# cnc_shield_v2.net
KiCad netlist of a schematic drawn in EAGLE
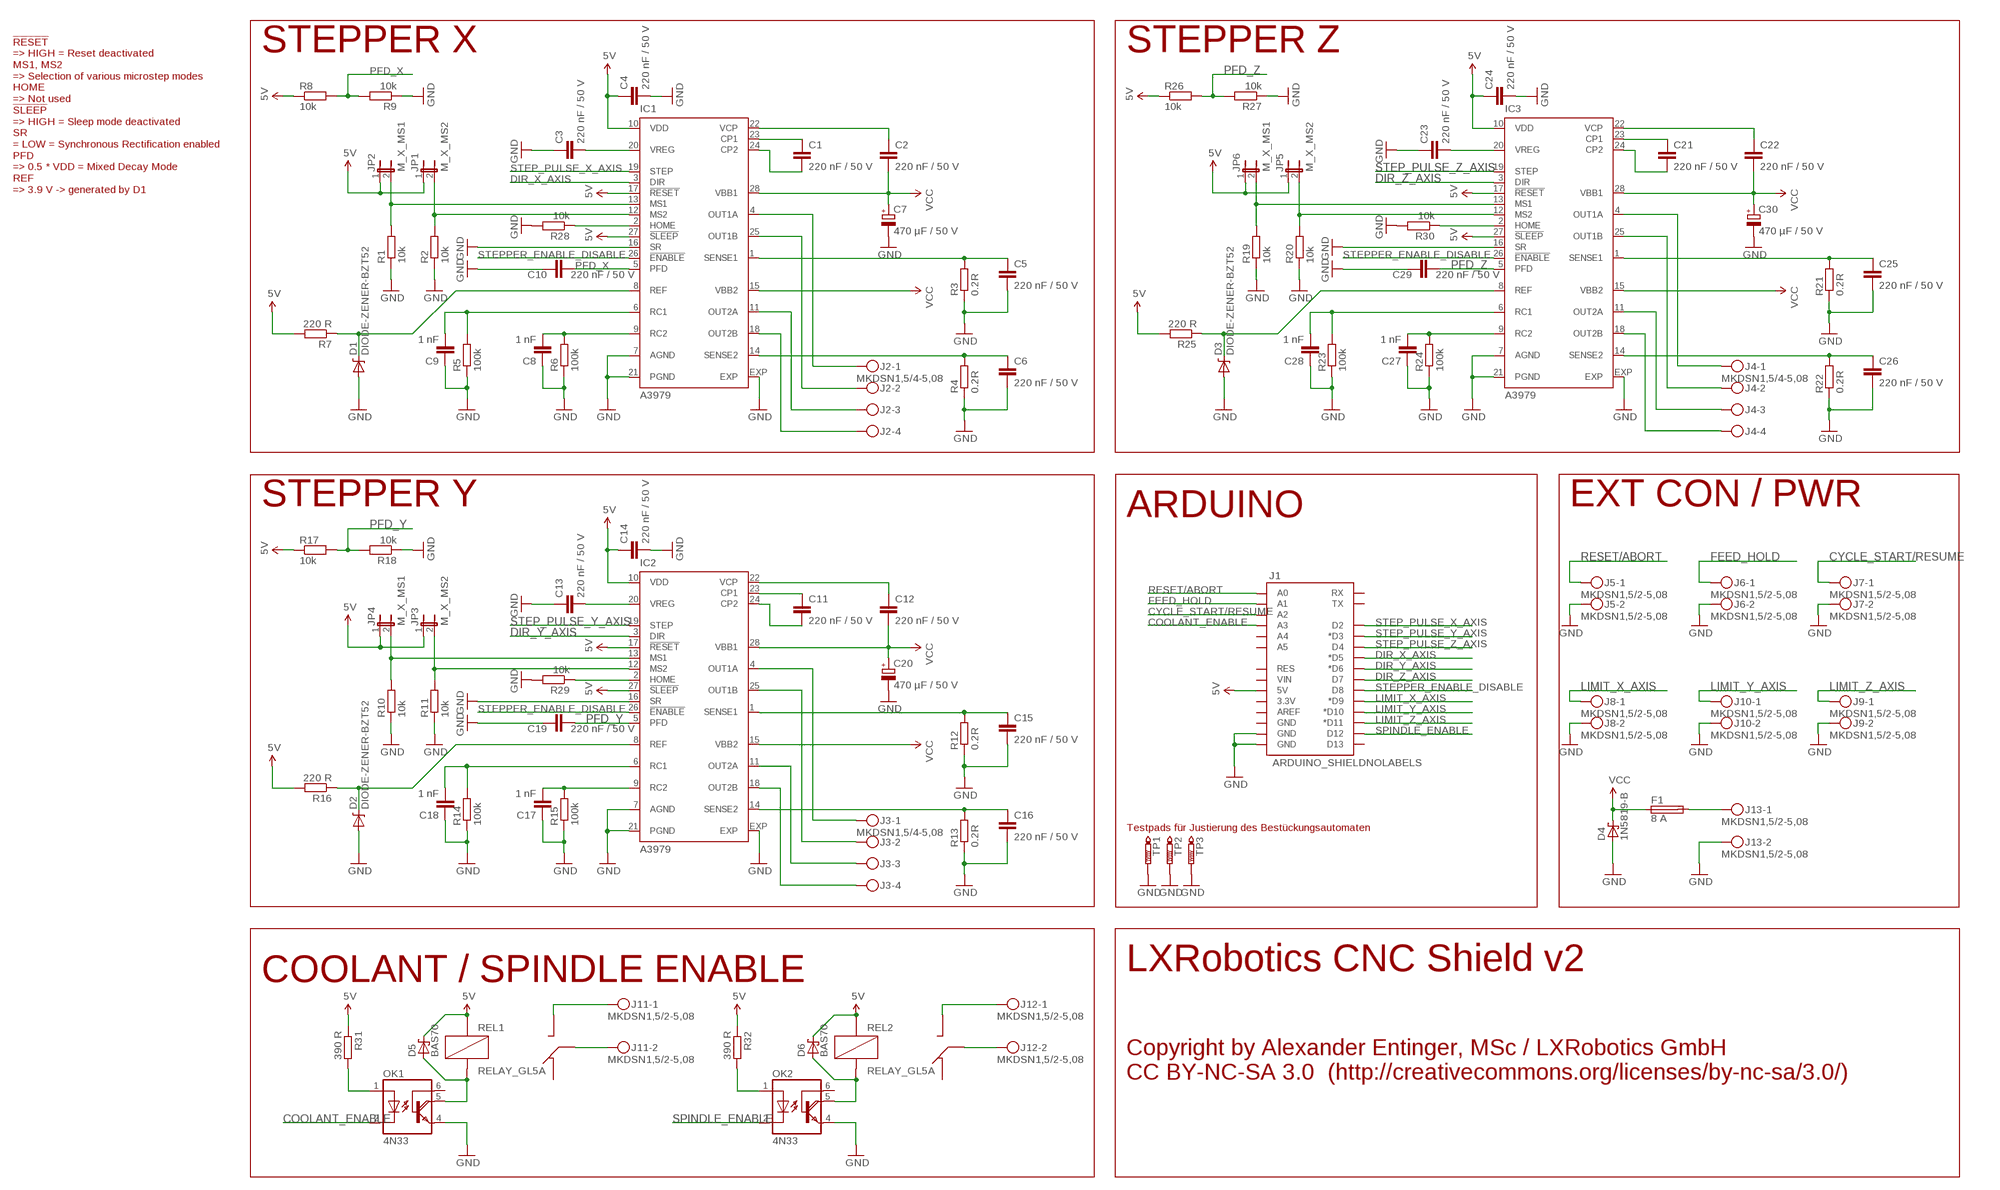
[diagram p0: schematic, sheet 1]

(export (version "E")
  (design (tool "Eeschema 10.0.6"))
  (components
    (comp (ref "C1")
      (value "220 nF / 50 V")
      (footprint "eagle-import:C0805K")
      (libsource (lib "eagle-import") (part "C-EUC0805K"))
    )
    (comp (ref "C2")
      (value "220 nF / 50 V")
      (footprint "eagle-import:C0805K")
      (libsource (lib "eagle-import") (part "C-EUC0805K"))
    )
    (comp (ref "C3")
      (value "220 nF / 50 V")
      (footprint "eagle-import:C0805K")
      (libsource (lib "eagle-import") (part "C-EUC0805K"))
    )
    (comp (ref "C4")
      (value "220 nF / 50 V")
      (footprint "eagle-import:C0805K")
      (libsource (lib "eagle-import") (part "C-EUC0805K"))
    )
    (comp (ref "C5")
      (value "220 nF / 50 V")
      (footprint "eagle-import:C0805K")
      (libsource (lib "eagle-import") (part "C-EUC0805K"))
    )
    (comp (ref "C6")
      (value "220 nF / 50 V")
      (footprint "eagle-import:C0805K")
      (libsource (lib "eagle-import") (part "C-EUC0805K"))
    )
    (comp (ref "C7")
      (value "470 µF / 50 V")
      (footprint "eagle-import:E5-13")
      (libsource (lib "eagle-import") (part "CPOL-EUE5-13"))
    )
    (comp (ref "C8")
      (value "1 nF")
      (footprint "eagle-import:C0805K")
      (libsource (lib "eagle-import") (part "C-EUC0805K"))
    )
    (comp (ref "C9")
      (value "1 nF")
      (footprint "eagle-import:C0805K")
      (libsource (lib "eagle-import") (part "C-EUC0805K"))
    )
    (comp (ref "C10")
      (value "220 nF / 50 V")
      (footprint "eagle-import:C0805K")
      (libsource (lib "eagle-import") (part "C-EUC0805K"))
    )
    (comp (ref "C11")
      (value "220 nF / 50 V")
      (footprint "eagle-import:C0805K")
      (libsource (lib "eagle-import") (part "C-EUC0805K"))
    )
    (comp (ref "C12")
      (value "220 nF / 50 V")
      (footprint "eagle-import:C0805K")
      (libsource (lib "eagle-import") (part "C-EUC0805K"))
    )
    (comp (ref "C13")
      (value "220 nF / 50 V")
      (footprint "eagle-import:C0805K")
      (libsource (lib "eagle-import") (part "C-EUC0805K"))
    )
    (comp (ref "C14")
      (value "220 nF / 50 V")
      (footprint "eagle-import:C0805K")
      (libsource (lib "eagle-import") (part "C-EUC0805K"))
    )
    (comp (ref "C15")
      (value "220 nF / 50 V")
      (footprint "eagle-import:C0805K")
      (libsource (lib "eagle-import") (part "C-EUC0805K"))
    )
    (comp (ref "C16")
      (value "220 nF / 50 V")
      (footprint "eagle-import:C0805K")
      (libsource (lib "eagle-import") (part "C-EUC0805K"))
    )
    (comp (ref "C17")
      (value "1 nF")
      (footprint "eagle-import:C0805K")
      (libsource (lib "eagle-import") (part "C-EUC0805K"))
    )
    (comp (ref "C18")
      (value "1 nF")
      (footprint "eagle-import:C0805K")
      (libsource (lib "eagle-import") (part "C-EUC0805K"))
    )
    (comp (ref "C19")
      (value "220 nF / 50 V")
      (footprint "eagle-import:C0805K")
      (libsource (lib "eagle-import") (part "C-EUC0805K"))
    )
    (comp (ref "C20")
      (value "470 µF / 50 V")
      (footprint "eagle-import:E5-13")
      (libsource (lib "eagle-import") (part "CPOL-EUE5-13"))
    )
    (comp (ref "C21")
      (value "220 nF / 50 V")
      (footprint "eagle-import:C0805K")
      (libsource (lib "eagle-import") (part "C-EUC0805K"))
    )
    (comp (ref "C22")
      (value "220 nF / 50 V")
      (footprint "eagle-import:C0805K")
      (libsource (lib "eagle-import") (part "C-EUC0805K"))
    )
    (comp (ref "C23")
      (value "220 nF / 50 V")
      (footprint "eagle-import:C0805K")
      (libsource (lib "eagle-import") (part "C-EUC0805K"))
    )
    (comp (ref "C24")
      (value "220 nF / 50 V")
      (footprint "eagle-import:C0805K")
      (libsource (lib "eagle-import") (part "C-EUC0805K"))
    )
    (comp (ref "C25")
      (value "220 nF / 50 V")
      (footprint "eagle-import:C0805K")
      (libsource (lib "eagle-import") (part "C-EUC0805K"))
    )
    (comp (ref "C26")
      (value "220 nF / 50 V")
      (footprint "eagle-import:C0805K")
      (libsource (lib "eagle-import") (part "C-EUC0805K"))
    )
    (comp (ref "C27")
      (value "1 nF")
      (footprint "eagle-import:C0805K")
      (libsource (lib "eagle-import") (part "C-EUC0805K"))
    )
    (comp (ref "C28")
      (value "1 nF")
      (footprint "eagle-import:C0805K")
      (libsource (lib "eagle-import") (part "C-EUC0805K"))
    )
    (comp (ref "C29")
      (value "220 nF / 50 V")
      (footprint "eagle-import:C0805K")
      (libsource (lib "eagle-import") (part "C-EUC0805K"))
    )
    (comp (ref "C30")
      (value "470 µF / 50 V")
      (footprint "eagle-import:E5-13")
      (libsource (lib "eagle-import") (part "CPOL-EUE5-13"))
    )
    (comp (ref "D1")
      (value "DIODE-ZENER-BZT52")
      (footprint "eagle-import:SOD-323")
      (libsource (lib "eagle-import") (part "DIODE-ZENER-BZT52"))
    )
    (comp (ref "D2")
      (value "DIODE-ZENER-BZT52")
      (footprint "eagle-import:SOD-323")
      (libsource (lib "eagle-import") (part "DIODE-ZENER-BZT52"))
    )
    (comp (ref "D3")
      (value "DIODE-ZENER-BZT52")
      (footprint "eagle-import:SOD-323")
      (libsource (lib "eagle-import") (part "DIODE-ZENER-BZT52"))
    )
    (comp (ref "D4")
      (value "1N5819-B")
      (footprint "eagle-import:DO41-7.6")
      (libsource (lib "eagle-import") (part "1N5819-B"))
    )
    (comp (ref "D5")
      (value "BAS70")
      (footprint "eagle-import:SOT23")
      (libsource (lib "eagle-import") (part "BAS70"))
    )
    (comp (ref "D6")
      (value "BAS70")
      (footprint "eagle-import:SOT23")
      (libsource (lib "eagle-import") (part "BAS70"))
    )
    (comp (ref "F1")
      (value "8 A")
      (footprint "eagle-import:SH22,5")
      (fields (field (name "MF") "SCHURTER") (field (name "MPN") "0031.8201"))
      (libsource (lib "eagle-import") (part "SH22,5"))
    )
    (comp (ref "IC1")
      (value "A3979")
      (footprint "eagle-import:TSSOP28")
      (libsource (lib "eagle-import") (part "A3979"))
    )
    (comp (ref "IC2")
      (value "A3979")
      (footprint "eagle-import:TSSOP28")
      (libsource (lib "eagle-import") (part "A3979"))
    )
    (comp (ref "IC3")
      (value "A3979")
      (footprint "eagle-import:TSSOP28")
      (libsource (lib "eagle-import") (part "A3979"))
    )
    (comp (ref "J1")
      (value "ARDUINO_SHIELDNOLABELS")
      (footprint "eagle-import:DUEMILANOVE_SHIELD_NOLABELS")
      (libsource (lib "eagle-import") (part "ARDUINO_SHIELDNOLABELS"))
    )
    (comp (ref "J2")
      (value "MKDSN1,5/4-5,08")
      (footprint "eagle-import:MKDSN1,5_4-5,08")
      (fields (field (name "MPN") "SMKDSN1,5/4-5,08"))
      (libsource (lib "eagle-import") (part "MKDSN1,5/4-5,08"))
    )
    (comp (ref "J3")
      (value "MKDSN1,5/4-5,08")
      (footprint "eagle-import:MKDSN1,5_4-5,08")
      (fields (field (name "MPN") "SMKDSN1,5/4-5,08"))
      (libsource (lib "eagle-import") (part "MKDSN1,5/4-5,08"))
    )
    (comp (ref "J4")
      (value "MKDSN1,5/4-5,08")
      (footprint "eagle-import:MKDSN1,5_4-5,08")
      (fields (field (name "MPN") "SMKDSN1,5/4-5,08"))
      (libsource (lib "eagle-import") (part "MKDSN1,5/4-5,08"))
    )
    (comp (ref "J5")
      (value "MKDSN1,5/2-5,08")
      (footprint "eagle-import:MKDSN1,5_2-5,08")
      (fields (field (name "MPN") "MKDSN 1,5/2-5.08"))
      (libsource (lib "eagle-import") (part "MKDSN1,5/2-5,08"))
    )
    (comp (ref "J6")
      (value "MKDSN1,5/2-5,08")
      (footprint "eagle-import:MKDSN1,5_2-5,08")
      (fields (field (name "MPN") "MKDSN 1,5/2-5.08"))
      (libsource (lib "eagle-import") (part "MKDSN1,5/2-5,08"))
    )
    (comp (ref "J7")
      (value "MKDSN1,5/2-5,08")
      (footprint "eagle-import:MKDSN1,5_2-5,08")
      (fields (field (name "MPN") "MKDSN 1,5/2-5.08"))
      (libsource (lib "eagle-import") (part "MKDSN1,5/2-5,08"))
    )
    (comp (ref "J8")
      (value "MKDSN1,5/2-5,08")
      (footprint "eagle-import:MKDSN1,5_2-5,08")
      (fields (field (name "MPN") "MKDSN 1,5/2-5.08"))
      (libsource (lib "eagle-import") (part "MKDSN1,5/2-5,08"))
    )
    (comp (ref "J9")
      (value "MKDSN1,5/2-5,08")
      (footprint "eagle-import:MKDSN1,5_2-5,08")
      (fields (field (name "MPN") "MKDSN 1,5/2-5.08"))
      (libsource (lib "eagle-import") (part "MKDSN1,5/2-5,08"))
    )
    (comp (ref "J10")
      (value "MKDSN1,5/2-5,08")
      (footprint "eagle-import:MKDSN1,5_2-5,08")
      (fields (field (name "MPN") "MKDSN 1,5/2-5.08"))
      (libsource (lib "eagle-import") (part "MKDSN1,5/2-5,08"))
    )
    (comp (ref "J11")
      (value "MKDSN1,5/2-5,08")
      (footprint "eagle-import:MKDSN1,5_2-5,08")
      (fields (field (name "MPN") "MKDSN 1,5/2-5.08"))
      (libsource (lib "eagle-import") (part "MKDSN1,5/2-5,08"))
    )
    (comp (ref "J12")
      (value "MKDSN1,5/2-5,08")
      (footprint "eagle-import:MKDSN1,5_2-5,08")
      (fields (field (name "MPN") "MKDSN 1,5/2-5.08"))
      (libsource (lib "eagle-import") (part "MKDSN1,5/2-5,08"))
    )
    (comp (ref "J13")
      (value "MKDSN1,5/2-5,08")
      (footprint "eagle-import:MKDSN1,5_2-5,08")
      (fields (field (name "MPN") "MKDSN 1,5/2-5.08"))
      (libsource (lib "eagle-import") (part "MKDSN1,5/2-5,08"))
    )
    (comp (ref "JP1")
      (value "M_X_MS2")
      (footprint "eagle-import:JP1")
      (libsource (lib "eagle-import") (part "JP1E"))
    )
    (comp (ref "JP2")
      (value "M_X_MS1")
      (footprint "eagle-import:JP1")
      (libsource (lib "eagle-import") (part "JP1E"))
    )
    (comp (ref "JP3")
      (value "M_X_MS2")
      (footprint "eagle-import:JP1")
      (libsource (lib "eagle-import") (part "JP1E"))
    )
    (comp (ref "JP4")
      (value "M_X_MS1")
      (footprint "eagle-import:JP1")
      (libsource (lib "eagle-import") (part "JP1E"))
    )
    (comp (ref "JP5")
      (value "M_X_MS2")
      (footprint "eagle-import:JP1")
      (libsource (lib "eagle-import") (part "JP1E"))
    )
    (comp (ref "JP6")
      (value "M_X_MS1")
      (footprint "eagle-import:JP1")
      (libsource (lib "eagle-import") (part "JP1E"))
    )
    (comp (ref "OK1")
      (value "4N33")
      (footprint "eagle-import:DIL06")
      (fields (field (name "MF") "VISHAY/TELEFUNKEN"))
      (libsource (lib "eagle-import") (part "4N33"))
    )
    (comp (ref "OK2")
      (value "4N33")
      (footprint "eagle-import:DIL06")
      (fields (field (name "MF") "VISHAY/TELEFUNKEN"))
      (libsource (lib "eagle-import") (part "4N33"))
    )
    (comp (ref "R1")
      (value "10k")
      (footprint "eagle-import:R0805")
      (libsource (lib "eagle-import") (part "R-EU_R0805"))
    )
    (comp (ref "R2")
      (value "10k")
      (footprint "eagle-import:R0805")
      (libsource (lib "eagle-import") (part "R-EU_R0805"))
    )
    (comp (ref "R3")
      (value "0.2R")
      (footprint "eagle-import:R2512")
      (libsource (lib "eagle-import") (part "R-EU_R2512"))
    )
    (comp (ref "R4")
      (value "0.2R")
      (footprint "eagle-import:R2512")
      (libsource (lib "eagle-import") (part "R-EU_R2512"))
    )
    (comp (ref "R5")
      (value "100k")
      (footprint "eagle-import:R0805")
      (libsource (lib "eagle-import") (part "R-EU_R0805"))
    )
    (comp (ref "R6")
      (value "100k")
      (footprint "eagle-import:R0805")
      (libsource (lib "eagle-import") (part "R-EU_R0805"))
    )
    (comp (ref "R7")
      (value "220 R")
      (footprint "eagle-import:R0805")
      (libsource (lib "eagle-import") (part "R-EU_R0805"))
    )
    (comp (ref "R8")
      (value "10k")
      (footprint "eagle-import:R0805")
      (libsource (lib "eagle-import") (part "R-EU_R0805"))
    )
    (comp (ref "R9")
      (value "10k")
      (footprint "eagle-import:R0805")
      (libsource (lib "eagle-import") (part "R-EU_R0805"))
    )
    (comp (ref "R10")
      (value "10k")
      (footprint "eagle-import:R0805")
      (libsource (lib "eagle-import") (part "R-EU_R0805"))
    )
    (comp (ref "R11")
      (value "10k")
      (footprint "eagle-import:R0805")
      (libsource (lib "eagle-import") (part "R-EU_R0805"))
    )
    (comp (ref "R12")
      (value "0.2R")
      (footprint "eagle-import:R2512")
      (libsource (lib "eagle-import") (part "R-EU_R2512"))
    )
    (comp (ref "R13")
      (value "0.2R")
      (footprint "eagle-import:R2512")
      (libsource (lib "eagle-import") (part "R-EU_R2512"))
    )
    (comp (ref "R14")
      (value "100k")
      (footprint "eagle-import:R0805")
      (libsource (lib "eagle-import") (part "R-EU_R0805"))
    )
    (comp (ref "R15")
      (value "100k")
      (footprint "eagle-import:R0805")
      (libsource (lib "eagle-import") (part "R-EU_R0805"))
    )
    (comp (ref "R16")
      (value "220 R")
      (footprint "eagle-import:R0805")
      (libsource (lib "eagle-import") (part "R-EU_R0805"))
    )
    (comp (ref "R17")
      (value "10k")
      (footprint "eagle-import:R0805")
      (libsource (lib "eagle-import") (part "R-EU_R0805"))
    )
    (comp (ref "R18")
      (value "10k")
      (footprint "eagle-import:R0805")
      (libsource (lib "eagle-import") (part "R-EU_R0805"))
    )
    (comp (ref "R19")
      (value "10k")
      (footprint "eagle-import:R0805")
      (libsource (lib "eagle-import") (part "R-EU_R0805"))
    )
    (comp (ref "R20")
      (value "10k")
      (footprint "eagle-import:R0805")
      (libsource (lib "eagle-import") (part "R-EU_R0805"))
    )
    (comp (ref "R21")
      (value "0.2R")
      (footprint "eagle-import:R2512")
      (libsource (lib "eagle-import") (part "R-EU_R2512"))
    )
    (comp (ref "R22")
      (value "0.2R")
      (footprint "eagle-import:R2512")
      (libsource (lib "eagle-import") (part "R-EU_R2512"))
    )
    (comp (ref "R23")
      (value "100k")
      (footprint "eagle-import:R0805")
      (libsource (lib "eagle-import") (part "R-EU_R0805"))
    )
    (comp (ref "R24")
      (value "100k")
      (footprint "eagle-import:R0805")
      (libsource (lib "eagle-import") (part "R-EU_R0805"))
    )
    (comp (ref "R25")
      (value "220 R")
      (footprint "eagle-import:R0805")
      (libsource (lib "eagle-import") (part "R-EU_R0805"))
    )
    (comp (ref "R26")
      (value "10k")
      (footprint "eagle-import:R0805")
      (libsource (lib "eagle-import") (part "R-EU_R0805"))
    )
    (comp (ref "R27")
      (value "10k")
      (footprint "eagle-import:R0805")
      (libsource (lib "eagle-import") (part "R-EU_R0805"))
    )
    (comp (ref "R28")
      (value "10k")
      (footprint "eagle-import:R0805")
      (libsource (lib "eagle-import") (part "R-EU_R0805"))
    )
    (comp (ref "R29")
      (value "10k")
      (footprint "eagle-import:R0805")
      (libsource (lib "eagle-import") (part "R-EU_R0805"))
    )
    (comp (ref "R30")
      (value "10k")
      (footprint "eagle-import:R0805")
      (libsource (lib "eagle-import") (part "R-EU_R0805"))
    )
    (comp (ref "R31")
      (value "390 R")
      (footprint "eagle-import:R0805")
      (libsource (lib "eagle-import") (part "R-EU_R0805"))
    )
    (comp (ref "R32")
      (value "390 R")
      (footprint "eagle-import:R0805")
      (libsource (lib "eagle-import") (part "R-EU_R0805"))
    )
    (comp (ref "REL1")
      (value "RELAY_GL5A")
      (footprint "eagle-import:RELAY_GL5A")
      (libsource (lib "eagle-import") (part "RELAY_GL5A"))
    )
    (comp (ref "REL2")
      (value "RELAY_GL5A")
      (footprint "eagle-import:RELAY_GL5A")
      (libsource (lib "eagle-import") (part "RELAY_GL5A"))
    )
    (comp (ref "TP1")
      (value "PTR1B1,27")
      (footprint "eagle-import:B1,27")
      (libsource (lib "eagle-import") (part "PTR1B1,27"))
    )
    (comp (ref "TP2")
      (value "PTR1B1,27")
      (footprint "eagle-import:B1,27")
      (libsource (lib "eagle-import") (part "PTR1B1,27"))
    )
    (comp (ref "TP3")
      (value "PTR1B1,27")
      (footprint "eagle-import:B1,27")
      (libsource (lib "eagle-import") (part "PTR1B1,27"))
    )
  )
  (nets
    (net (code "1") (name "/COOLANT_ENABLE") (class "Default")
      (node (ref "J1") (pin "A3") (pinfunction "A3_A3") (pintype "bidirectional"))
      (node (ref "OK1") (pin "2") (pinfunction "C_2") (pintype "passive"))
    )
    (net (code "2") (name "/CYCLE_START{slash}RESUME") (class "Default")
      (node (ref "J1") (pin "A2") (pinfunction "A2_A2") (pintype "bidirectional"))
      (node (ref "J7") (pin "1") (pinfunction "KL_1") (pintype "passive"))
    )
    (net (code "3") (name "/DIR_X_AXIS") (class "Default")
      (node (ref "IC1") (pin "3") (pinfunction "DIR_3") (pintype "input"))
      (node (ref "J1") (pin "D5") (pinfunction "*D5_D5") (pintype "bidirectional"))
    )
    (net (code "4") (name "/DIR_Y_AXIS") (class "Default")
      (node (ref "IC2") (pin "3") (pinfunction "DIR_3") (pintype "input"))
      (node (ref "J1") (pin "D6") (pinfunction "*D6_D6") (pintype "bidirectional"))
    )
    (net (code "5") (name "/DIR_Z_AXIS") (class "Default")
      (node (ref "IC3") (pin "3") (pinfunction "DIR_3") (pintype "input"))
      (node (ref "J1") (pin "D7") (pinfunction "D7_D7") (pintype "bidirectional"))
    )
    (net (code "6") (name "/FEED_HOLD") (class "Default")
      (node (ref "J1") (pin "A1") (pinfunction "A1_A1") (pintype "bidirectional"))
      (node (ref "J6") (pin "1") (pinfunction "KL_1") (pintype "passive"))
    )
    (net (code "7") (name "/LIMIT_X_AXIS") (class "Default")
      (node (ref "J1") (pin "D9") (pinfunction "*D9_D9") (pintype "bidirectional"))
      (node (ref "J8") (pin "1") (pinfunction "KL_1") (pintype "passive"))
    )
    (net (code "8") (name "/LIMIT_Y_AXIS") (class "Default")
      (node (ref "J1") (pin "D10") (pinfunction "*D10_D10") (pintype "bidirectional"))
      (node (ref "J10") (pin "1") (pinfunction "KL_1") (pintype "passive"))
    )
    (net (code "9") (name "/LIMIT_Z_AXIS") (class "Default")
      (node (ref "J1") (pin "D11") (pinfunction "*D11_D11") (pintype "bidirectional"))
      (node (ref "J9") (pin "1") (pinfunction "KL_1") (pintype "passive"))
    )
    (net (code "10") (name "/PFD_X") (class "Default")
      (node (ref "C10") (pin "2") (pinfunction "2_2") (pintype "passive"))
      (node (ref "IC1") (pin "5") (pinfunction "PFD_5") (pintype "input"))
      (node (ref "R8") (pin "2") (pinfunction "2_2") (pintype "passive"))
      (node (ref "R9") (pin "2") (pinfunction "2_2") (pintype "passive"))
    )
    (net (code "11") (name "/PFD_Y") (class "Default")
      (node (ref "C19") (pin "2") (pinfunction "2_2") (pintype "passive"))
      (node (ref "IC2") (pin "5") (pinfunction "PFD_5") (pintype "input"))
      (node (ref "R17") (pin "2") (pinfunction "2_2") (pintype "passive"))
      (node (ref "R18") (pin "2") (pinfunction "2_2") (pintype "passive"))
    )
    (net (code "12") (name "/PFD_Z") (class "Default")
      (node (ref "C29") (pin "2") (pinfunction "2_2") (pintype "passive"))
      (node (ref "IC3") (pin "5") (pinfunction "PFD_5") (pintype "input"))
      (node (ref "R26") (pin "2") (pinfunction "2_2") (pintype "passive"))
      (node (ref "R27") (pin "2") (pinfunction "2_2") (pintype "passive"))
    )
    (net (code "13") (name "/RESET{slash}ABORT") (class "Default")
      (node (ref "J1") (pin "A0") (pinfunction "A0_A0") (pintype "bidirectional"))
      (node (ref "J5") (pin "1") (pinfunction "KL_1") (pintype "passive"))
    )
    (net (code "14") (name "/SPINDLE_ENABLE") (class "Default")
      (node (ref "J1") (pin "D12") (pinfunction "D12_D12") (pintype "bidirectional"))
      (node (ref "OK2") (pin "2") (pinfunction "C_2") (pintype "passive"))
    )
    (net (code "15") (name "/STEPPER_ENABLE_DISABLE") (class "Default")
      (node (ref "IC1") (pin "26") (pinfunction "~{ENABLE}_26") (pintype "input"))
      (node (ref "IC2") (pin "26") (pinfunction "~{ENABLE}_26") (pintype "input"))
      (node (ref "IC3") (pin "26") (pinfunction "~{ENABLE}_26") (pintype "input"))
      (node (ref "J1") (pin "D8") (pinfunction "D8_D8") (pintype "bidirectional"))
    )
    (net (code "16") (name "/STEP_PULSE_X_AXIS") (class "Default")
      (node (ref "IC1") (pin "19") (pinfunction "STEP_19") (pintype "input"))
      (node (ref "J1") (pin "D2") (pinfunction "D2_D2") (pintype "bidirectional"))
    )
    (net (code "17") (name "/STEP_PULSE_Y_AXIS") (class "Default")
      (node (ref "IC2") (pin "19") (pinfunction "STEP_19") (pintype "input"))
      (node (ref "J1") (pin "D3") (pinfunction "*D3_D3") (pintype "bidirectional"))
    )
    (net (code "18") (name "/STEP_PULSE_Z_AXIS") (class "Default")
      (node (ref "IC3") (pin "19") (pinfunction "STEP_19") (pintype "input"))
      (node (ref "J1") (pin "D4") (pinfunction "D4_D4") (pintype "bidirectional"))
    )
    (net (code "19") (name "5V") (class "Default")
      (node (ref "C14") (pin "1") (pinfunction "1_1") (pintype "passive"))
      (node (ref "C24") (pin "1") (pinfunction "1_1") (pintype "passive"))
      (node (ref "C4") (pin "1") (pinfunction "1_1") (pintype "passive"))
      (node (ref "D5") (pin "3") (pinfunction "C_3") (pintype "passive"))
      (node (ref "D6") (pin "3") (pinfunction "C_3") (pintype "passive"))
      (node (ref "IC1") (pin "10") (pinfunction "VDD_10") (pintype "power_in"))
      (node (ref "IC1") (pin "17") (pinfunction "~{RESET}_17") (pintype "input"))
      (node (ref "IC1") (pin "27") (pinfunction "~{SLEEP}_27") (pintype "input"))
      (node (ref "IC2") (pin "10") (pinfunction "VDD_10") (pintype "power_in"))
      (node (ref "IC2") (pin "17") (pinfunction "~{RESET}_17") (pintype "input"))
      (node (ref "IC2") (pin "27") (pinfunction "~{SLEEP}_27") (pintype "input"))
      (node (ref "IC3") (pin "10") (pinfunction "VDD_10") (pintype "power_in"))
      (node (ref "IC3") (pin "17") (pinfunction "~{RESET}_17") (pintype "input"))
      (node (ref "IC3") (pin "27") (pinfunction "~{SLEEP}_27") (pintype "input"))
      (node (ref "J1") (pin "5V") (pinfunction "5V_5V") (pintype "bidirectional"))
      (node (ref "JP1") (pin "1") (pinfunction "1_1") (pintype "passive"))
      (node (ref "JP2") (pin "1") (pinfunction "1_1") (pintype "passive"))
      (node (ref "JP3") (pin "1") (pinfunction "1_1") (pintype "passive"))
      (node (ref "JP4") (pin "1") (pinfunction "1_1") (pintype "passive"))
      (node (ref "JP5") (pin "1") (pinfunction "1_1") (pintype "passive"))
      (node (ref "JP6") (pin "1") (pinfunction "1_1") (pintype "passive"))
      (node (ref "R16") (pin "2") (pinfunction "2_2") (pintype "passive"))
      (node (ref "R17") (pin "1") (pinfunction "1_1") (pintype "passive"))
      (node (ref "R25") (pin "2") (pinfunction "2_2") (pintype "passive"))
      (node (ref "R26") (pin "1") (pinfunction "1_1") (pintype "passive"))
      (node (ref "R31") (pin "1") (pinfunction "1_1") (pintype "passive"))
      (node (ref "R32") (pin "1") (pinfunction "1_1") (pintype "passive"))
      (node (ref "R7") (pin "2") (pinfunction "2_2") (pintype "passive"))
      (node (ref "R8") (pin "1") (pinfunction "1_1") (pintype "passive"))
      (node (ref "REL1") (pin "R2") (pinfunction "R2_COIL1_R2") (pintype "bidirectional"))
      (node (ref "REL2") (pin "R2") (pinfunction "R2_COIL1_R2") (pintype "bidirectional"))
    )
    (net (code "20") (name "GND") (class "Default")
      (node (ref "C10") (pin "1") (pinfunction "1_1") (pintype "passive"))
      (node (ref "C13") (pin "1") (pinfunction "1_1") (pintype "passive"))
      (node (ref "C14") (pin "2") (pinfunction "2_2") (pintype "passive"))
      (node (ref "C15") (pin "2") (pinfunction "2_2") (pintype "passive"))
      (node (ref "C16") (pin "2") (pinfunction "2_2") (pintype "passive"))
      (node (ref "C17") (pin "1") (pinfunction "1_1") (pintype "passive"))
      (node (ref "C18") (pin "1") (pinfunction "1_1") (pintype "passive"))
      (node (ref "C19") (pin "1") (pinfunction "1_1") (pintype "passive"))
      (node (ref "C20") (pin "-") (pinfunction "-_-") (pintype "passive"))
      (node (ref "C23") (pin "1") (pinfunction "1_1") (pintype "passive"))
      (node (ref "C24") (pin "2") (pinfunction "2_2") (pintype "passive"))
      (node (ref "C25") (pin "2") (pinfunction "2_2") (pintype "passive"))
      (node (ref "C26") (pin "2") (pinfunction "2_2") (pintype "passive"))
      (node (ref "C27") (pin "1") (pinfunction "1_1") (pintype "passive"))
      (node (ref "C28") (pin "1") (pinfunction "1_1") (pintype "passive"))
      (node (ref "C29") (pin "1") (pinfunction "1_1") (pintype "passive"))
      (node (ref "C3") (pin "1") (pinfunction "1_1") (pintype "passive"))
      (node (ref "C30") (pin "-") (pinfunction "-_-") (pintype "passive"))
      (node (ref "C4") (pin "2") (pinfunction "2_2") (pintype "passive"))
      (node (ref "C5") (pin "2") (pinfunction "2_2") (pintype "passive"))
      (node (ref "C6") (pin "2") (pinfunction "2_2") (pintype "passive"))
      (node (ref "C7") (pin "-") (pinfunction "-_-") (pintype "passive"))
      (node (ref "C8") (pin "1") (pinfunction "1_1") (pintype "passive"))
      (node (ref "C9") (pin "1") (pinfunction "1_1") (pintype "passive"))
      (node (ref "D1") (pin "2") (pinfunction "A_2") (pintype "passive"))
      (node (ref "D2") (pin "2") (pinfunction "A_2") (pintype "passive"))
      (node (ref "D3") (pin "2") (pinfunction "A_2") (pintype "passive"))
      (node (ref "D4") (pin "A") (pinfunction "A_A") (pintype "passive"))
      (node (ref "IC1") (pin "16") (pinfunction "SR_16") (pintype "input"))
      (node (ref "IC1") (pin "21") (pinfunction "PGND_21") (pintype "power_in"))
      (node (ref "IC1") (pin "7") (pinfunction "AGND_7") (pintype "power_in"))
      (node (ref "IC1") (pin "EXP") (pinfunction "EXP_EXP") (pintype "power_in"))
      (node (ref "IC2") (pin "16") (pinfunction "SR_16") (pintype "input"))
      (node (ref "IC2") (pin "21") (pinfunction "PGND_21") (pintype "power_in"))
      (node (ref "IC2") (pin "7") (pinfunction "AGND_7") (pintype "power_in"))
      (node (ref "IC2") (pin "EXP") (pinfunction "EXP_EXP") (pintype "power_in"))
      (node (ref "IC3") (pin "16") (pinfunction "SR_16") (pintype "input"))
      (node (ref "IC3") (pin "21") (pinfunction "PGND_21") (pintype "power_in"))
      (node (ref "IC3") (pin "7") (pinfunction "AGND_7") (pintype "power_in"))
      (node (ref "IC3") (pin "EXP") (pinfunction "EXP_EXP") (pintype "power_in"))
      (node (ref "J1") (pin "GND@0") (pinfunction "GND_GND@0") (pintype "bidirectional"))
      (node (ref "J1") (pin "GND@1") (pinfunction "GND_GND@1") (pintype "bidirectional"))
      (node (ref "J10") (pin "2") (pinfunction "KL_2") (pintype "passive"))
      (node (ref "J13") (pin "2") (pinfunction "KL_2") (pintype "passive"))
      (node (ref "J5") (pin "2") (pinfunction "KL_2") (pintype "passive"))
      (node (ref "J6") (pin "2") (pinfunction "KL_2") (pintype "passive"))
      (node (ref "J7") (pin "2") (pinfunction "KL_2") (pintype "passive"))
      (node (ref "J8") (pin "2") (pinfunction "KL_2") (pintype "passive"))
      (node (ref "J9") (pin "2") (pinfunction "KL_2") (pintype "passive"))
      (node (ref "OK1") (pin "4") (pinfunction "E_4") (pintype "passive"))
      (node (ref "OK2") (pin "4") (pinfunction "E_4") (pintype "passive"))
      (node (ref "R1") (pin "1") (pinfunction "1_1") (pintype "passive"))
      (node (ref "R10") (pin "1") (pinfunction "1_1") (pintype "passive"))
      (node (ref "R11") (pin "1") (pinfunction "1_1") (pintype "passive"))
      (node (ref "R12") (pin "1") (pinfunction "1_1") (pintype "passive"))
      (node (ref "R13") (pin "1") (pinfunction "1_1") (pintype "passive"))
      (node (ref "R14") (pin "1") (pinfunction "1_1") (pintype "passive"))
      (node (ref "R15") (pin "1") (pinfunction "1_1") (pintype "passive"))
      (node (ref "R18") (pin "1") (pinfunction "1_1") (pintype "passive"))
      (node (ref "R19") (pin "1") (pinfunction "1_1") (pintype "passive"))
      (node (ref "R2") (pin "1") (pinfunction "1_1") (pintype "passive"))
      (node (ref "R20") (pin "1") (pinfunction "1_1") (pintype "passive"))
      (node (ref "R21") (pin "1") (pinfunction "1_1") (pintype "passive"))
      (node (ref "R22") (pin "1") (pinfunction "1_1") (pintype "passive"))
      (node (ref "R23") (pin "1") (pinfunction "1_1") (pintype "passive"))
      (node (ref "R24") (pin "1") (pinfunction "1_1") (pintype "passive"))
      (node (ref "R27") (pin "1") (pinfunction "1_1") (pintype "passive"))
      (node (ref "R28") (pin "2") (pinfunction "2_2") (pintype "passive"))
      (node (ref "R29") (pin "2") (pinfunction "2_2") (pintype "passive"))
      (node (ref "R3") (pin "1") (pinfunction "1_1") (pintype "passive"))
      (node (ref "R30") (pin "2") (pinfunction "2_2") (pintype "passive"))
      (node (ref "R4") (pin "1") (pinfunction "1_1") (pintype "passive"))
      (node (ref "R5") (pin "1") (pinfunction "1_1") (pintype "passive"))
      (node (ref "R6") (pin "1") (pinfunction "1_1") (pintype "passive"))
      (node (ref "R9") (pin "1") (pinfunction "1_1") (pintype "passive"))
      (node (ref "TP1") (pin "TP") (pinfunction "TP_TP") (pintype "input"))
      (node (ref "TP2") (pin "TP") (pinfunction "TP_TP") (pintype "input"))
      (node (ref "TP3") (pin "TP") (pinfunction "TP_TP") (pintype "input"))
    )
    (net (code "21") (name "Net-(D1-C)") (class "Default")
      (node (ref "D1") (pin "1") (pinfunction "C_1") (pintype "passive"))
      (node (ref "IC1") (pin "8") (pinfunction "REF_8") (pintype "input"))
      (node (ref "R7") (pin "1") (pinfunction "1_1") (pintype "passive"))
    )
    (net (code "22") (name "Net-(D2-C)") (class "Default")
      (node (ref "D2") (pin "1") (pinfunction "C_1") (pintype "passive"))
      (node (ref "IC2") (pin "8") (pinfunction "REF_8") (pintype "input"))
      (node (ref "R16") (pin "1") (pinfunction "1_1") (pintype "passive"))
    )
    (net (code "23") (name "Net-(D3-C)") (class "Default")
      (node (ref "D3") (pin "1") (pinfunction "C_1") (pintype "passive"))
      (node (ref "IC3") (pin "8") (pinfunction "REF_8") (pintype "input"))
      (node (ref "R25") (pin "1") (pinfunction "1_1") (pintype "passive"))
    )
    (net (code "24") (name "Net-(D5-A)") (class "Default")
      (node (ref "D5") (pin "1") (pinfunction "A_1") (pintype "passive"))
      (node (ref "OK1") (pin "5") (pinfunction "COL_5") (pintype "passive"))
      (node (ref "REL1") (pin "R5") (pinfunction "R5_COIL2_R5") (pintype "bidirectional"))
    )
    (net (code "25") (name "Net-(D6-A)") (class "Default")
      (node (ref "D6") (pin "1") (pinfunction "A_1") (pintype "passive"))
      (node (ref "OK2") (pin "5") (pinfunction "COL_5") (pintype "passive"))
      (node (ref "REL2") (pin "R5") (pinfunction "R5_COIL2_R5") (pintype "bidirectional"))
    )
    (net (code "26") (name "Net-(IC1-CP1)") (class "Default")
      (node (ref "C1") (pin "1") (pinfunction "1_1") (pintype "passive"))
      (node (ref "IC1") (pin "23") (pinfunction "CP1_23") (pintype "passive"))
    )
    (net (code "27") (name "Net-(IC1-CP2)") (class "Default")
      (node (ref "C1") (pin "2") (pinfunction "2_2") (pintype "passive"))
      (node (ref "IC1") (pin "24") (pinfunction "CP2_24") (pintype "passive"))
    )
    (net (code "28") (name "Net-(IC1-HOME)") (class "Default")
      (node (ref "IC1") (pin "2") (pinfunction "HOME_2") (pintype "input"))
      (node (ref "R28") (pin "1") (pinfunction "1_1") (pintype "passive"))
    )
    (net (code "29") (name "Net-(IC1-MS1)") (class "Default")
      (node (ref "IC1") (pin "13") (pinfunction "MS1_13") (pintype "input"))
      (node (ref "JP2") (pin "2") (pinfunction "2_2") (pintype "passive"))
      (node (ref "R1") (pin "2") (pinfunction "2_2") (pintype "passive"))
    )
    (net (code "30") (name "Net-(IC1-MS2)") (class "Default")
      (node (ref "IC1") (pin "12") (pinfunction "MS2_12") (pintype "input"))
      (node (ref "JP1") (pin "2") (pinfunction "2_2") (pintype "passive"))
      (node (ref "R2") (pin "2") (pinfunction "2_2") (pintype "passive"))
    )
    (net (code "31") (name "Net-(IC1-OUT1A)") (class "Default")
      (node (ref "IC1") (pin "4") (pinfunction "OUT1A_4") (pintype "output"))
      (node (ref "J2") (pin "1") (pinfunction "KL_1") (pintype "passive"))
    )
    (net (code "32") (name "Net-(IC1-OUT1B)") (class "Default")
      (node (ref "IC1") (pin "25") (pinfunction "OUT1B_25") (pintype "output"))
      (node (ref "J2") (pin "2") (pinfunction "KL_2") (pintype "passive"))
    )
    (net (code "33") (name "Net-(IC1-OUT2A)") (class "Default")
      (node (ref "IC1") (pin "11") (pinfunction "OUT2A_11") (pintype "output"))
      (node (ref "J2") (pin "3") (pinfunction "KL_3") (pintype "passive"))
    )
    (net (code "34") (name "Net-(IC1-OUT2B)") (class "Default")
      (node (ref "IC1") (pin "18") (pinfunction "OUT2B_18") (pintype "output"))
      (node (ref "J2") (pin "4") (pinfunction "KL_4") (pintype "passive"))
    )
    (net (code "35") (name "Net-(IC1-RC1)") (class "Default")
      (node (ref "C9") (pin "2") (pinfunction "2_2") (pintype "passive"))
      (node (ref "IC1") (pin "6") (pinfunction "RC1_6") (pintype "passive"))
      (node (ref "R5") (pin "2") (pinfunction "2_2") (pintype "passive"))
    )
    (net (code "36") (name "Net-(IC1-RC2)") (class "Default")
      (node (ref "C8") (pin "2") (pinfunction "2_2") (pintype "passive"))
      (node (ref "IC1") (pin "9") (pinfunction "RC2_9") (pintype "passive"))
      (node (ref "R6") (pin "2") (pinfunction "2_2") (pintype "passive"))
    )
    (net (code "37") (name "Net-(IC1-SENSE1)") (class "Default")
      (node (ref "C5") (pin "1") (pinfunction "1_1") (pintype "passive"))
      (node (ref "IC1") (pin "1") (pinfunction "SENSE1_1") (pintype "input"))
      (node (ref "R3") (pin "2") (pinfunction "2_2") (pintype "passive"))
    )
    (net (code "38") (name "Net-(IC1-SENSE2)") (class "Default")
      (node (ref "C6") (pin "1") (pinfunction "1_1") (pintype "passive"))
      (node (ref "IC1") (pin "14") (pinfunction "SENSE2_14") (pintype "input"))
      (node (ref "R4") (pin "2") (pinfunction "2_2") (pintype "passive"))
    )
    (net (code "39") (name "Net-(IC1-VCP)") (class "Default")
      (node (ref "C2") (pin "1") (pinfunction "1_1") (pintype "passive"))
      (node (ref "IC1") (pin "22") (pinfunction "VCP_22") (pintype "passive"))
    )
    (net (code "40") (name "Net-(IC1-VREG)") (class "Default")
      (node (ref "C3") (pin "2") (pinfunction "2_2") (pintype "passive"))
      (node (ref "IC1") (pin "20") (pinfunction "VREG_20") (pintype "power_in"))
    )
    (net (code "41") (name "Net-(IC2-CP1)") (class "Default")
      (node (ref "C11") (pin "1") (pinfunction "1_1") (pintype "passive"))
      (node (ref "IC2") (pin "23") (pinfunction "CP1_23") (pintype "passive"))
    )
    (net (code "42") (name "Net-(IC2-CP2)") (class "Default")
      (node (ref "C11") (pin "2") (pinfunction "2_2") (pintype "passive"))
      (node (ref "IC2") (pin "24") (pinfunction "CP2_24") (pintype "passive"))
    )
    (net (code "43") (name "Net-(IC2-HOME)") (class "Default")
      (node (ref "IC2") (pin "2") (pinfunction "HOME_2") (pintype "input"))
      (node (ref "R29") (pin "1") (pinfunction "1_1") (pintype "passive"))
    )
    (net (code "44") (name "Net-(IC2-MS1)") (class "Default")
      (node (ref "IC2") (pin "13") (pinfunction "MS1_13") (pintype "input"))
      (node (ref "JP4") (pin "2") (pinfunction "2_2") (pintype "passive"))
      (node (ref "R10") (pin "2") (pinfunction "2_2") (pintype "passive"))
    )
    (net (code "45") (name "Net-(IC2-MS2)") (class "Default")
      (node (ref "IC2") (pin "12") (pinfunction "MS2_12") (pintype "input"))
      (node (ref "JP3") (pin "2") (pinfunction "2_2") (pintype "passive"))
      (node (ref "R11") (pin "2") (pinfunction "2_2") (pintype "passive"))
    )
    (net (code "46") (name "Net-(IC2-OUT1A)") (class "Default")
      (node (ref "IC2") (pin "4") (pinfunction "OUT1A_4") (pintype "output"))
      (node (ref "J3") (pin "1") (pinfunction "KL_1") (pintype "passive"))
    )
    (net (code "47") (name "Net-(IC2-OUT1B)") (class "Default")
      (node (ref "IC2") (pin "25") (pinfunction "OUT1B_25") (pintype "output"))
      (node (ref "J3") (pin "2") (pinfunction "KL_2") (pintype "passive"))
    )
    (net (code "48") (name "Net-(IC2-OUT2A)") (class "Default")
      (node (ref "IC2") (pin "11") (pinfunction "OUT2A_11") (pintype "output"))
      (node (ref "J3") (pin "3") (pinfunction "KL_3") (pintype "passive"))
    )
    (net (code "49") (name "Net-(IC2-OUT2B)") (class "Default")
      (node (ref "IC2") (pin "18") (pinfunction "OUT2B_18") (pintype "output"))
      (node (ref "J3") (pin "4") (pinfunction "KL_4") (pintype "passive"))
    )
    (net (code "50") (name "Net-(IC2-RC1)") (class "Default")
      (node (ref "C18") (pin "2") (pinfunction "2_2") (pintype "passive"))
      (node (ref "IC2") (pin "6") (pinfunction "RC1_6") (pintype "passive"))
      (node (ref "R14") (pin "2") (pinfunction "2_2") (pintype "passive"))
    )
    (net (code "51") (name "Net-(IC2-RC2)") (class "Default")
      (node (ref "C17") (pin "2") (pinfunction "2_2") (pintype "passive"))
      (node (ref "IC2") (pin "9") (pinfunction "RC2_9") (pintype "passive"))
      (node (ref "R15") (pin "2") (pinfunction "2_2") (pintype "passive"))
    )
    (net (code "52") (name "Net-(IC2-SENSE1)") (class "Default")
      (node (ref "C15") (pin "1") (pinfunction "1_1") (pintype "passive"))
      (node (ref "IC2") (pin "1") (pinfunction "SENSE1_1") (pintype "input"))
      (node (ref "R12") (pin "2") (pinfunction "2_2") (pintype "passive"))
    )
    (net (code "53") (name "Net-(IC2-SENSE2)") (class "Default")
      (node (ref "C16") (pin "1") (pinfunction "1_1") (pintype "passive"))
      (node (ref "IC2") (pin "14") (pinfunction "SENSE2_14") (pintype "input"))
      (node (ref "R13") (pin "2") (pinfunction "2_2") (pintype "passive"))
    )
    (net (code "54") (name "Net-(IC2-VCP)") (class "Default")
      (node (ref "C12") (pin "1") (pinfunction "1_1") (pintype "passive"))
      (node (ref "IC2") (pin "22") (pinfunction "VCP_22") (pintype "passive"))
    )
    (net (code "55") (name "Net-(IC2-VREG)") (class "Default")
      (node (ref "C13") (pin "2") (pinfunction "2_2") (pintype "passive"))
      (node (ref "IC2") (pin "20") (pinfunction "VREG_20") (pintype "power_in"))
    )
    (net (code "56") (name "Net-(IC3-CP1)") (class "Default")
      (node (ref "C21") (pin "1") (pinfunction "1_1") (pintype "passive"))
      (node (ref "IC3") (pin "23") (pinfunction "CP1_23") (pintype "passive"))
    )
    (net (code "57") (name "Net-(IC3-CP2)") (class "Default")
      (node (ref "C21") (pin "2") (pinfunction "2_2") (pintype "passive"))
      (node (ref "IC3") (pin "24") (pinfunction "CP2_24") (pintype "passive"))
    )
    (net (code "58") (name "Net-(IC3-HOME)") (class "Default")
      (node (ref "IC3") (pin "2") (pinfunction "HOME_2") (pintype "input"))
      (node (ref "R30") (pin "1") (pinfunction "1_1") (pintype "passive"))
    )
    (net (code "59") (name "Net-(IC3-MS1)") (class "Default")
      (node (ref "IC3") (pin "13") (pinfunction "MS1_13") (pintype "input"))
      (node (ref "JP6") (pin "2") (pinfunction "2_2") (pintype "passive"))
      (node (ref "R19") (pin "2") (pinfunction "2_2") (pintype "passive"))
    )
    (net (code "60") (name "Net-(IC3-MS2)") (class "Default")
      (node (ref "IC3") (pin "12") (pinfunction "MS2_12") (pintype "input"))
      (node (ref "JP5") (pin "2") (pinfunction "2_2") (pintype "passive"))
      (node (ref "R20") (pin "2") (pinfunction "2_2") (pintype "passive"))
    )
    (net (code "61") (name "Net-(IC3-OUT1A)") (class "Default")
      (node (ref "IC3") (pin "4") (pinfunction "OUT1A_4") (pintype "output"))
      (node (ref "J4") (pin "1") (pinfunction "KL_1") (pintype "passive"))
    )
    (net (code "62") (name "Net-(IC3-OUT1B)") (class "Default")
      (node (ref "IC3") (pin "25") (pinfunction "OUT1B_25") (pintype "output"))
      (node (ref "J4") (pin "2") (pinfunction "KL_2") (pintype "passive"))
    )
    (net (code "63") (name "Net-(IC3-OUT2A)") (class "Default")
      (node (ref "IC3") (pin "11") (pinfunction "OUT2A_11") (pintype "output"))
      (node (ref "J4") (pin "3") (pinfunction "KL_3") (pintype "passive"))
    )
    (net (code "64") (name "Net-(IC3-OUT2B)") (class "Default")
      (node (ref "IC3") (pin "18") (pinfunction "OUT2B_18") (pintype "output"))
      (node (ref "J4") (pin "4") (pinfunction "KL_4") (pintype "passive"))
    )
    (net (code "65") (name "Net-(IC3-RC1)") (class "Default")
      (node (ref "C28") (pin "2") (pinfunction "2_2") (pintype "passive"))
      (node (ref "IC3") (pin "6") (pinfunction "RC1_6") (pintype "passive"))
      (node (ref "R23") (pin "2") (pinfunction "2_2") (pintype "passive"))
    )
    (net (code "66") (name "Net-(IC3-RC2)") (class "Default")
      (node (ref "C27") (pin "2") (pinfunction "2_2") (pintype "passive"))
      (node (ref "IC3") (pin "9") (pinfunction "RC2_9") (pintype "passive"))
      (node (ref "R24") (pin "2") (pinfunction "2_2") (pintype "passive"))
    )
    (net (code "67") (name "Net-(IC3-SENSE1)") (class "Default")
      (node (ref "C25") (pin "1") (pinfunction "1_1") (pintype "passive"))
      (node (ref "IC3") (pin "1") (pinfunction "SENSE1_1") (pintype "input"))
      (node (ref "R21") (pin "2") (pinfunction "2_2") (pintype "passive"))
    )
    (net (code "68") (name "Net-(IC3-SENSE2)") (class "Default")
      (node (ref "C26") (pin "1") (pinfunction "1_1") (pintype "passive"))
      (node (ref "IC3") (pin "14") (pinfunction "SENSE2_14") (pintype "input"))
      (node (ref "R22") (pin "2") (pinfunction "2_2") (pintype "passive"))
    )
    (net (code "69") (name "Net-(IC3-VCP)") (class "Default")
      (node (ref "C22") (pin "1") (pinfunction "1_1") (pintype "passive"))
      (node (ref "IC3") (pin "22") (pinfunction "VCP_22") (pintype "passive"))
    )
    (net (code "70") (name "Net-(IC3-VREG)") (class "Default")
      (node (ref "C23") (pin "2") (pinfunction "2_2") (pintype "passive"))
      (node (ref "IC3") (pin "20") (pinfunction "VREG_20") (pintype "power_in"))
    )
    (net (code "71") (name "Net-(J11A-KL)") (class "Default")
      (node (ref "J11") (pin "1") (pinfunction "KL_1") (pintype "passive"))
      (node (ref "REL1") (pin "R3") (pinfunction "R3_SW_R3") (pintype "bidirectional"))
    )
    (net (code "72") (name "Net-(J11B-KL)") (class "Default")
      (node (ref "J11") (pin "2") (pinfunction "KL_2") (pintype "passive"))
      (node (ref "REL1") (pin "R1") (pinfunction "R1_COMMON_R1") (pintype "bidirectional"))
    )
    (net (code "73") (name "Net-(J12A-KL)") (class "Default")
      (node (ref "J12") (pin "1") (pinfunction "KL_1") (pintype "passive"))
      (node (ref "REL2") (pin "R3") (pinfunction "R3_SW_R3") (pintype "bidirectional"))
    )
    (net (code "74") (name "Net-(J12B-KL)") (class "Default")
      (node (ref "J12") (pin "2") (pinfunction "KL_2") (pintype "passive"))
      (node (ref "REL2") (pin "R1") (pinfunction "R1_COMMON_R1") (pintype "bidirectional"))
    )
    (net (code "75") (name "Net-(J13A-KL)") (class "Default")
      (node (ref "F1") (pin "2") (pinfunction "2_2") (pintype "passive"))
      (node (ref "J13") (pin "1") (pinfunction "KL_1") (pintype "passive"))
    )
    (net (code "76") (name "Net-(OK1-A)") (class "Default")
      (node (ref "OK1") (pin "1") (pinfunction "A_1") (pintype "passive"))
      (node (ref "R31") (pin "2") (pinfunction "2_2") (pintype "passive"))
    )
    (net (code "77") (name "Net-(OK2-A)") (class "Default")
      (node (ref "OK2") (pin "1") (pinfunction "A_1") (pintype "passive"))
      (node (ref "R32") (pin "2") (pinfunction "2_2") (pintype "passive"))
    )
    (net (code "78") (name "VCC") (class "Default")
      (node (ref "C12") (pin "2") (pinfunction "2_2") (pintype "passive"))
      (node (ref "C2") (pin "2") (pinfunction "2_2") (pintype "passive"))
      (node (ref "C20") (pin "+") (pinfunction "+_+") (pintype "passive"))
      (node (ref "C22") (pin "2") (pinfunction "2_2") (pintype "passive"))
      (node (ref "C30") (pin "+") (pinfunction "+_+") (pintype "passive"))
      (node (ref "C7") (pin "+") (pinfunction "+_+") (pintype "passive"))
      (node (ref "D4") (pin "C") (pinfunction "C_C") (pintype "passive"))
      (node (ref "F1") (pin "1") (pinfunction "1_1") (pintype "passive"))
      (node (ref "IC1") (pin "15") (pinfunction "VBB2_15") (pintype "power_in"))
      (node (ref "IC1") (pin "28") (pinfunction "VBB1_28") (pintype "power_in"))
      (node (ref "IC2") (pin "15") (pinfunction "VBB2_15") (pintype "power_in"))
      (node (ref "IC2") (pin "28") (pinfunction "VBB1_28") (pintype "power_in"))
      (node (ref "IC3") (pin "15") (pinfunction "VBB2_15") (pintype "power_in"))
      (node (ref "IC3") (pin "28") (pinfunction "VBB1_28") (pintype "power_in"))
    )
    (net (code "79") (name "unconnected-(J1-GND-PadGND@2)") (class "Default")
      (node (ref "J1") (pin "GND@2") (pinfunction "GND_GND@2") (pintype "bidirectional"))
    )
    (net (code "80") (name "unconnected-(J1-Pad3.3V)") (class "Default")
      (node (ref "J1") (pin "3.3V") (pinfunction "3.3V_3.3V") (pintype "bidirectional"))
    )
    (net (code "81") (name "unconnected-(J1-PadA4)") (class "Default")
      (node (ref "J1") (pin "A4") (pinfunction "A4_A4") (pintype "bidirectional"))
    )
    (net (code "82") (name "unconnected-(J1-PadA5)") (class "Default")
      (node (ref "J1") (pin "A5") (pinfunction "A5_A5") (pintype "bidirectional"))
    )
    (net (code "83") (name "unconnected-(J1-PadAREF)") (class "Default")
      (node (ref "J1") (pin "AREF") (pinfunction "AREF_AREF") (pintype "bidirectional"))
    )
    (net (code "84") (name "unconnected-(J1-PadD13)") (class "Default")
      (node (ref "J1") (pin "D13") (pinfunction "D13_D13") (pintype "bidirectional"))
    )
    (net (code "85") (name "unconnected-(J1-PadRES)") (class "Default")
      (node (ref "J1") (pin "RES") (pinfunction "RES_RES") (pintype "bidirectional"))
    )
    (net (code "86") (name "unconnected-(J1-PadRX)") (class "Default")
      (node (ref "J1") (pin "RX") (pinfunction "RX_RX") (pintype "bidirectional"))
    )
    (net (code "87") (name "unconnected-(J1-PadTX)") (class "Default")
      (node (ref "J1") (pin "TX") (pinfunction "TX_TX") (pintype "bidirectional"))
    )
    (net (code "88") (name "unconnected-(J1-PadVIN)") (class "Default")
      (node (ref "J1") (pin "VIN") (pinfunction "VIN_VIN") (pintype "bidirectional"))
    )
    (net (code "89") (name "unconnected-(OK1-B-Pad6)") (class "Default")
      (node (ref "OK1") (pin "6") (pinfunction "B_6") (pintype "passive"))
    )
    (net (code "90") (name "unconnected-(OK2-B-Pad6)") (class "Default")
      (node (ref "OK2") (pin "6") (pinfunction "B_6") (pintype "passive"))
    )
    (net (code "91") (name "unconnected-(REL1-R4_SW-PadR4)") (class "Default")
      (node (ref "REL1") (pin "R4") (pinfunction "R4_SW_R4") (pintype "bidirectional"))
    )
    (net (code "92") (name "unconnected-(REL2-R4_SW-PadR4)") (class "Default")
      (node (ref "REL2") (pin "R4") (pinfunction "R4_SW_R4") (pintype "bidirectional"))
    )
  )
)
